# 3V3SwitchingRegulator.net
KiCad netlist of a schematic drawn in Altium Designer
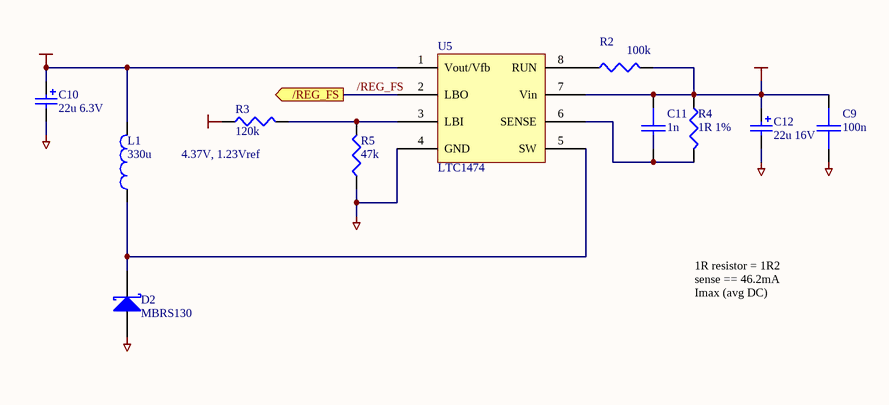
[diagram p0: 3V3SwitchingRegulator.SchDoc]

(export (version "E")
  (design (tool "Eeschema 10.0.6"))
  (components
    (comp (ref "C9")
      (value "100n")
      (footprint "0603")
      (description "Capacitor")
      (fields (field (name "MANUFACTURER") "Generic Components") (field (name "PUBLISHER") "Altium Limited"))
      (libsource (lib "Miscellaneous Devices") (part "CAP"))
    )
    (comp (ref "C10")
      (value "22u 6.3V")
      (footprint "MCCT-CASEC")
      (description "Polarized Capacitor (Surface Mount)")
      (fields (field (name "MANUFACTURER") "Generic Components") (field (name "PUBLISHER") "Altium Limited"))
      (libsource (lib "Miscellaneous Devices") (part "Cap Pol3"))
    )
    (comp (ref "C11")
      (value "1n")
      (footprint "0603")
      (description "Capacitor")
      (fields (field (name "MANUFACTURER") "Generic Components") (field (name "PUBLISHER") "Altium Limited"))
      (libsource (lib "Miscellaneous Devices") (part "CAP"))
    )
    (comp (ref "C12")
      (value "22u 16V")
      (footprint "MCCT-CASEC")
      (description "Polarized Capacitor (Surface Mount)")
      (fields (field (name "MANUFACTURER") "Generic Components") (field (name "PUBLISHER") "Altium Limited"))
      (libsource (lib "Miscellaneous Devices") (part "Cap Pol3"))
    )
    (comp (ref "D2")
      (value "MBRS130")
      (footprint "SMB")
      (description "Schottky Diode")
      (fields (field (name "MANUFACTURER") "Generic Components") (field (name "PUBLISHER") "Altium Limited"))
      (libsource (lib "Miscellaneous Devices") (part "D SCHOTTKY"))
    )
    (comp (ref "L1")
      (value "330u")
      (footprint "1812")
      (description "Inductor")
      (fields (field (name "MANUFACTURER") "Generic Components") (field (name "PUBLISHER") "Altium Limited"))
      (libsource (lib "Miscellaneous Devices") (part "Inductor"))
    )
    (comp (ref "R2")
      (value "100k")
      (footprint "0603")
      (description "Resistor")
      (libsource (lib "RCLDQ") (part "RES1"))
    )
    (comp (ref "R3")
      (value "120k")
      (footprint "0603")
      (description "Resistor")
      (libsource (lib "RCLDQ") (part "Res1"))
    )
    (comp (ref "R4")
      (value "1R 1%")
      (footprint "0603")
      (description "Resistor")
      (fields (field (name "MANUFACTURER") "Generic Components") (field (name "PUBLISHER") "Altium Limited"))
      (libsource (lib "Miscellaneous Devices") (part "RES1"))
    )
    (comp (ref "R5")
      (value "47k")
      (footprint "0603")
      (description "Resistor")
      (libsource (lib "RCLDQ") (part "RES1"))
    )
    (comp (ref "U5")
      (value "LTC1474")
      (footprint "TSOP8")
      (description "Step-down converter, LTC1474CMS8-3.3")
      (libsource (lib "MiscellaneousIC") (part "LTC1474"))
    )
  )
  (nets
    (net (code "1") (name "/{slash}REG_FS") (class "Default")
      (node (ref "U5") (pin "2") (pinfunction "LBO_2") (pintype "passive"))
    )
    (net (code "2") (name "3V3") (class "Default")
      (node (ref "C10") (pin "1") (pinfunction "1_1") (pintype "passive"))
      (node (ref "L1") (pin "2") (pinfunction "2_2") (pintype "passive"))
      (node (ref "U5") (pin "1") (pinfunction "Vout/Vfb_1") (pintype "passive"))
    )
    (net (code "3") (name "5V") (class "Default")
      (node (ref "C11") (pin "1") (pinfunction "1_1") (pintype "passive"))
      (node (ref "C12") (pin "1") (pinfunction "1_1") (pintype "passive"))
      (node (ref "C9") (pin "1") (pinfunction "1_1") (pintype "passive"))
      (node (ref "R2") (pin "2") (pinfunction "2_2") (pintype "passive"))
      (node (ref "R3") (pin "1") (pinfunction "1_1") (pintype "passive"))
      (node (ref "R4") (pin "1") (pinfunction "1_1") (pintype "passive"))
      (node (ref "U5") (pin "7") (pinfunction "Vin_7") (pintype "passive"))
    )
    (net (code "4") (name "GND") (class "Default")
      (node (ref "C10") (pin "2") (pinfunction "2_2") (pintype "passive"))
      (node (ref "C12") (pin "2") (pinfunction "2_2") (pintype "passive"))
      (node (ref "C9") (pin "2") (pinfunction "2_2") (pintype "passive"))
      (node (ref "D2") (pin "A") (pinfunction "A_A") (pintype "passive"))
      (node (ref "R5") (pin "1") (pinfunction "1_1") (pintype "passive"))
      (node (ref "U5") (pin "4") (pinfunction "GND_4") (pintype "passive"))
    )
    (net (code "5") (name "Net-(U5-LBI)") (class "Default")
      (node (ref "R3") (pin "2") (pinfunction "2_2") (pintype "passive"))
      (node (ref "R5") (pin "2") (pinfunction "2_2") (pintype "passive"))
      (node (ref "U5") (pin "3") (pinfunction "LBI_3") (pintype "passive"))
    )
    (net (code "6") (name "Net-(U5-RUN)") (class "Default")
      (node (ref "R2") (pin "1") (pinfunction "1_1") (pintype "passive"))
      (node (ref "U5") (pin "8") (pinfunction "RUN_8") (pintype "passive"))
    )
    (net (code "7") (name "Net-(U5-SENSE)") (class "Default")
      (node (ref "C11") (pin "2") (pinfunction "2_2") (pintype "passive"))
      (node (ref "R4") (pin "2") (pinfunction "2_2") (pintype "passive"))
      (node (ref "U5") (pin "6") (pinfunction "SENSE_6") (pintype "passive"))
    )
    (net (code "8") (name "Net-(U5-SW)") (class "Default")
      (node (ref "D2") (pin "K") (pinfunction "K_K") (pintype "passive"))
      (node (ref "L1") (pin "1") (pinfunction "1_1") (pintype "passive"))
      (node (ref "U5") (pin "5") (pinfunction "SW_5") (pintype "passive"))
    )
  )
)
